# MCU.net
KiCad netlist of a schematic drawn in Altium Designer
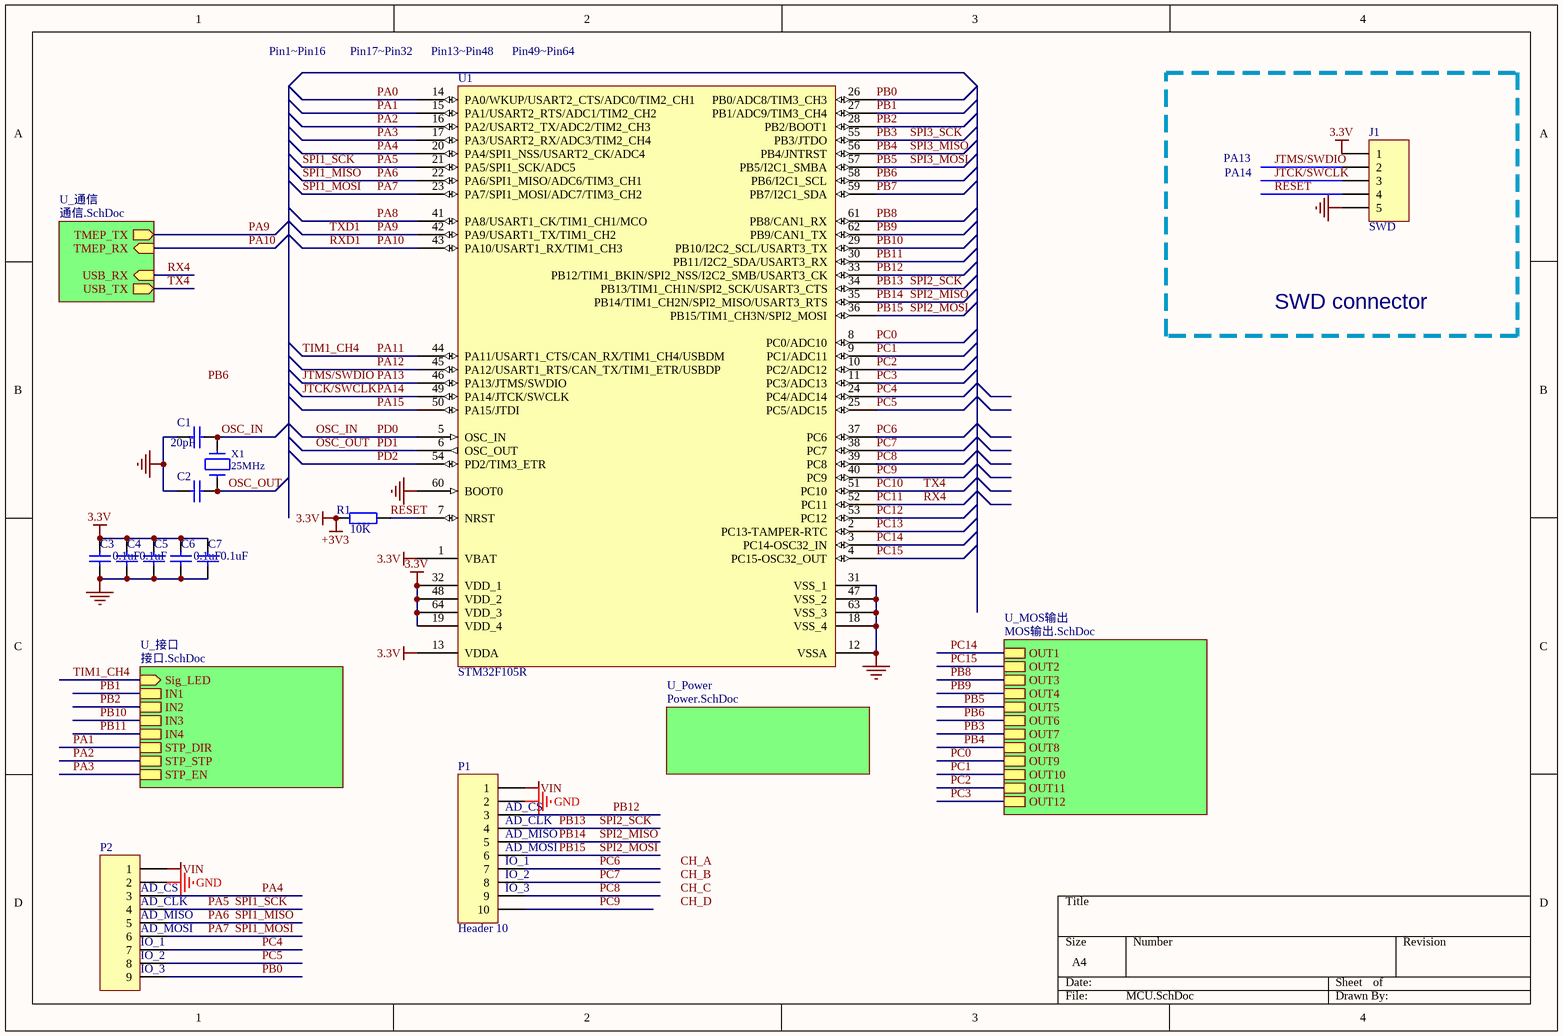
[diagram p0: MCU.SchDoc]

(export (version "E")
  (design (tool "Eeschema 10.0.6"))
  (components
    (comp (ref "C1")
      (value "20pF")
      (footprint "1608C")
      (description "Capacitor")
      (fields (field (name "PUBLISHER") "Altium Limited"))
      (libsource (lib "*") (part "Cap"))
    )
    (comp (ref "C2")
      (value "20pF")
      (footprint "1608C")
      (description "Capacitor")
      (fields (field (name "PUBLISHER") "Altium Limited"))
      (libsource (lib "*") (part "Cap"))
    )
    (comp (ref "C3")
      (value "0.1uF")
      (footprint "1608C")
      (description "Capacitor")
      (fields (field (name "PUBLISHER") "Altium Limited"))
      (libsource (lib "*") (part "Cap"))
    )
    (comp (ref "C4")
      (value "0.1uF")
      (footprint "1608C")
      (description "Capacitor")
      (fields (field (name "PUBLISHER") "Altium Limited"))
      (libsource (lib "*") (part "Cap"))
    )
    (comp (ref "C5")
      (value "0.1uF")
      (footprint "1608C")
      (description "Capacitor")
      (fields (field (name "PUBLISHER") "Altium Limited"))
      (libsource (lib "*") (part "Cap"))
    )
    (comp (ref "C6")
      (value "0.1uF")
      (footprint "1608C")
      (description "Capacitor")
      (fields (field (name "PUBLISHER") "Altium Limited"))
      (libsource (lib "*") (part "Cap"))
    )
    (comp (ref "C7")
      (value "0.1uF")
      (footprint "1608C")
      (description "Capacitor")
      (fields (field (name "PUBLISHER") "Altium Limited"))
      (libsource (lib "*") (part "Cap"))
    )
    (comp (ref "J1")
      (value "SWD")
      (footprint "ch2.5/5")
      (description "Header, 5-Pin")
      (fields (field (name "PUBLISHER") "Altium Limited"))
      (libsource (lib "Miscellaneous Connectors") (part "Header 5"))
    )
    (comp (ref "P1")
      (value "Header 10")
      (footprint "FPC-10B")
      (description "Header, 10-Pin")
      (fields (field (name "PUBLISHER") "Altium Limited"))
      (libsource (lib "Miscellaneous Connectors") (part "Header 10"))
    )
    (comp (ref "P2")
      (value "Header 9")
      (footprint "FPC-9B")
      (description "Header, 9-Pin")
      (fields (field (name "PUBLISHER") "Altium Limited"))
      (libsource (lib "Miscellaneous Connectors") (part "Header 9"))
    )
    (comp (ref "R1")
      (value "10K")
      (footprint "1608")
      (description "Resistor")
      (fields (field (name "PUBLISHER") "Altium Limited"))
      (libsource (lib "*") (part "Res2"))
    )
    (comp (ref "U1")
      (value "STM32F105R")
      (footprint "LQFP64_M")
      (libsource (lib "Schlib1") (part "STM32F105R"))
    )
    (comp (ref "X1") (value "25MHz") (footprint "SMD2_50X32") (libsource (lib "*") (part "CRYSTAL")))
  )
  (nets
    (net (code "1") (name "+3V3") (class "Default")
      (node (ref "C3") (pin "2") (pinfunction "2_2") (pintype "passive"))
      (node (ref "C4") (pin "2") (pinfunction "2_2") (pintype "passive"))
      (node (ref "C5") (pin "2") (pinfunction "2_2") (pintype "passive"))
      (node (ref "C6") (pin "2") (pinfunction "2_2") (pintype "passive"))
      (node (ref "C7") (pin "2") (pinfunction "2_2") (pintype "passive"))
      (node (ref "J1") (pin "1") (pinfunction "1_1") (pintype "passive"))
      (node (ref "R1") (pin "1") (pinfunction "1_1") (pintype "passive"))
      (node (ref "U1") (pin "1") (pinfunction "VBAT_1") (pintype "power_in"))
      (node (ref "U1") (pin "13") (pinfunction "VDDA_13") (pintype "power_in"))
      (node (ref "U1") (pin "19") (pinfunction "VDD_4_19") (pintype "power_in"))
      (node (ref "U1") (pin "32") (pinfunction "VDD_1_32") (pintype "power_in"))
      (node (ref "U1") (pin "48") (pinfunction "VDD_2_48") (pintype "power_in"))
      (node (ref "U1") (pin "64") (pinfunction "VDD_3_64") (pintype "power_in"))
    )
    (net (code "6") (name "/JTCK{slash}SWCLK") (class "Default")
      (node (ref "J1") (pin "3") (pinfunction "3_3") (pintype "passive"))
      (node (ref "U1") (pin "49") (pinfunction "PA14/JTCK/SWCLK_49") (pintype "bidirectional"))
    )
    (net (code "7") (name "/JTMS{slash}SWDIO") (class "Default")
      (node (ref "J1") (pin "2") (pinfunction "2_2") (pintype "passive"))
      (node (ref "U1") (pin "46") (pinfunction "PA13/JTMS/SWDIO_46") (pintype "bidirectional"))
    )
    (net (code "8") (name "/OSC_IN") (class "Default")
      (node (ref "C1") (pin "1") (pinfunction "1_1") (pintype "passive"))
      (node (ref "U1") (pin "5") (pinfunction "OSC_IN_5") (pintype "input"))
      (node (ref "X1") (pin "2") (pintype "passive"))
    )
    (net (code "9") (name "/OSC_OUT") (class "Default")
      (node (ref "C2") (pin "1") (pinfunction "1_1") (pintype "passive"))
      (node (ref "U1") (pin "6") (pinfunction "OSC_OUT_6") (pintype "output"))
      (node (ref "X1") (pin "1") (pintype "passive"))
    )
    (net (code "10") (name "/PA0") (class "Default")
      (node (ref "U1") (pin "14") (pinfunction "PA0/WKUP/USART2_CTS/ADC0/TIM2_CH1_14") (pintype "bidirectional"))
    )
    (net (code "11") (name "/PA1") (class "Default")
      (node (ref "U1") (pin "15") (pinfunction "PA1/USART2_RTS/ADC1/TIM2_CH2_15") (pintype "bidirectional"))
    )
    (net (code "12") (name "/PA2") (class "Default")
      (node (ref "U1") (pin "16") (pinfunction "PA2/USART2_TX/ADC2/TIM2_CH3_16") (pintype "bidirectional"))
    )
    (net (code "13") (name "/PA3") (class "Default")
      (node (ref "U1") (pin "17") (pinfunction "PA3/USART2_RX/ADC3/TIM2_CH4_17") (pintype "bidirectional"))
    )
    (net (code "14") (name "/PA4") (class "Default")
      (node (ref "P2") (pin "3") (pinfunction "3_3") (pintype "passive"))
      (node (ref "U1") (pin "20") (pinfunction "PA4/SPI1_NSS/USART2_CK/ADC4_20") (pintype "bidirectional"))
    )
    (net (code "15") (name "/PA5") (class "Default")
      (node (ref "P2") (pin "4") (pinfunction "4_4") (pintype "passive"))
      (node (ref "U1") (pin "21") (pinfunction "PA5/SPI1_SCK/ADC5_21") (pintype "bidirectional"))
    )
    (net (code "16") (name "/PA6") (class "Default")
      (node (ref "P2") (pin "5") (pinfunction "5_5") (pintype "passive"))
      (node (ref "U1") (pin "22") (pinfunction "PA6/SPI1_MISO/ADC6/TIM3_CH1_22") (pintype "bidirectional"))
    )
    (net (code "17") (name "/PA7") (class "Default")
      (node (ref "P2") (pin "6") (pinfunction "6_6") (pintype "passive"))
      (node (ref "U1") (pin "23") (pinfunction "PA7/SPI1_MOSI/ADC7/TIM3_CH2_23") (pintype "bidirectional"))
    )
    (net (code "18") (name "/PA8") (class "Default")
      (node (ref "U1") (pin "41") (pinfunction "PA8/USART1_CK/TIM1_CH1/MCO_41") (pintype "bidirectional"))
    )
    (net (code "19") (name "/PA9") (class "Default")
      (node (ref "U1") (pin "42") (pinfunction "PA9/USART1_TX/TIM1_CH2_42") (pintype "bidirectional"))
    )
    (net (code "20") (name "/PA10") (class "Default")
      (node (ref "U1") (pin "43") (pinfunction "PA10/USART1_RX/TIM1_CH3_43") (pintype "bidirectional"))
    )
    (net (code "21") (name "/PA11") (class "Default")
      (node (ref "U1") (pin "44") (pinfunction "PA11/USART1_CTS/CAN_RX/TIM1_CH4/USBDM_44") (pintype "bidirectional"))
    )
    (net (code "22") (name "/PA12") (class "Default")
      (node (ref "U1") (pin "45") (pinfunction "PA12/USART1_RTS/CAN_TX/TIM1_ETR/USBDP_45") (pintype "bidirectional"))
    )
    (net (code "23") (name "/PA15") (class "Default")
      (node (ref "U1") (pin "50") (pinfunction "PA15/JTDI_50") (pintype "bidirectional"))
    )
    (net (code "24") (name "/PB0") (class "Default")
      (node (ref "P2") (pin "9") (pinfunction "9_9") (pintype "passive"))
      (node (ref "U1") (pin "26") (pinfunction "PB0/ADC8/TIM3_CH3_26") (pintype "bidirectional"))
    )
    (net (code "25") (name "/PB1") (class "Default")
      (node (ref "U1") (pin "27") (pinfunction "PB1/ADC9/TIM3_CH4_27") (pintype "bidirectional"))
    )
    (net (code "26") (name "/PB2") (class "Default")
      (node (ref "U1") (pin "28") (pinfunction "PB2/BOOT1_28") (pintype "bidirectional"))
    )
    (net (code "27") (name "/PB3") (class "Default")
      (node (ref "U1") (pin "55") (pinfunction "PB3/JTDO_55") (pintype "bidirectional"))
    )
    (net (code "28") (name "/PB4") (class "Default")
      (node (ref "U1") (pin "56") (pinfunction "PB4/JNTRST_56") (pintype "bidirectional"))
    )
    (net (code "29") (name "/PB5") (class "Default")
      (node (ref "U1") (pin "57") (pinfunction "PB5/I2C1_SMBA_57") (pintype "bidirectional"))
    )
    (net (code "30") (name "/PB6") (class "Default")
      (node (ref "U1") (pin "58") (pinfunction "PB6/I2C1_SCL_58") (pintype "bidirectional"))
    )
    (net (code "31") (name "/PB7") (class "Default")
      (node (ref "U1") (pin "59") (pinfunction "PB7/I2C1_SDA_59") (pintype "bidirectional"))
    )
    (net (code "32") (name "/PB8") (class "Default")
      (node (ref "U1") (pin "61") (pinfunction "PB8/CAN1_RX_61") (pintype "bidirectional"))
    )
    (net (code "33") (name "/PB9") (class "Default")
      (node (ref "U1") (pin "62") (pinfunction "PB9/CAN1_TX_62") (pintype "bidirectional"))
    )
    (net (code "34") (name "/PB10") (class "Default")
      (node (ref "U1") (pin "29") (pinfunction "PB10/I2C2_SCL/USART3_TX_29") (pintype "bidirectional"))
    )
    (net (code "35") (name "/PB11") (class "Default")
      (node (ref "U1") (pin "30") (pinfunction "PB11/I2C2_SDA/USART3_RX_30") (pintype "bidirectional"))
    )
    (net (code "36") (name "/PB12") (class "Default")
      (node (ref "P1") (pin "3") (pinfunction "3_3") (pintype "passive"))
      (node (ref "U1") (pin "33") (pinfunction "PB12/TIM1_BKIN/SPI2_NSS/I2C2_SMB/USART3_CK_33") (pintype "bidirectional"))
    )
    (net (code "37") (name "/PB13") (class "Default")
      (node (ref "P1") (pin "4") (pinfunction "4_4") (pintype "passive"))
      (node (ref "U1") (pin "34") (pinfunction "PB13/TIM1_CH1N/SPI2_SCK/USART3_CTS_34") (pintype "bidirectional"))
    )
    (net (code "38") (name "/PB14") (class "Default")
      (node (ref "P1") (pin "5") (pinfunction "5_5") (pintype "passive"))
      (node (ref "U1") (pin "35") (pinfunction "PB14/TIM1_CH2N/SPI2_MISO/USART3_RTS_35") (pintype "bidirectional"))
    )
    (net (code "39") (name "/PB15") (class "Default")
      (node (ref "P1") (pin "6") (pinfunction "6_6") (pintype "passive"))
      (node (ref "U1") (pin "36") (pinfunction "PB15/TIM1_CH3N/SPI2_MOSI_36") (pintype "bidirectional"))
    )
    (net (code "40") (name "/PC0") (class "Default")
      (node (ref "U1") (pin "8") (pinfunction "PC0/ADC10_8") (pintype "bidirectional"))
    )
    (net (code "41") (name "/PC1") (class "Default")
      (node (ref "U1") (pin "9") (pinfunction "PC1/ADC11_9") (pintype "bidirectional"))
    )
    (net (code "42") (name "/PC2") (class "Default")
      (node (ref "U1") (pin "10") (pinfunction "PC2/ADC12_10") (pintype "bidirectional"))
    )
    (net (code "43") (name "/PC3") (class "Default")
      (node (ref "U1") (pin "11") (pinfunction "PC3/ADC13_11") (pintype "bidirectional"))
    )
    (net (code "44") (name "/PC4") (class "Default")
      (node (ref "P2") (pin "7") (pinfunction "7_7") (pintype "passive"))
      (node (ref "U1") (pin "24") (pinfunction "PC4/ADC14_24") (pintype "bidirectional"))
    )
    (net (code "45") (name "/PC5") (class "Default")
      (node (ref "P2") (pin "8") (pinfunction "8_8") (pintype "passive"))
      (node (ref "U1") (pin "25") (pinfunction "PC5/ADC15_25") (pintype "bidirectional"))
    )
    (net (code "46") (name "/PC6") (class "Default")
      (node (ref "P1") (pin "7") (pinfunction "7_7") (pintype "passive"))
      (node (ref "U1") (pin "37") (pinfunction "PC6_37") (pintype "bidirectional"))
    )
    (net (code "47") (name "/PC7") (class "Default")
      (node (ref "P1") (pin "8") (pinfunction "8_8") (pintype "passive"))
      (node (ref "U1") (pin "38") (pinfunction "PC7_38") (pintype "bidirectional"))
    )
    (net (code "48") (name "/PC8") (class "Default")
      (node (ref "P1") (pin "9") (pinfunction "9_9") (pintype "passive"))
      (node (ref "U1") (pin "39") (pinfunction "PC8_39") (pintype "bidirectional"))
    )
    (net (code "49") (name "/PC9") (class "Default")
      (node (ref "P1") (pin "10") (pinfunction "10_10") (pintype "passive"))
      (node (ref "U1") (pin "40") (pinfunction "PC9_40") (pintype "bidirectional"))
    )
    (net (code "50") (name "/PC10") (class "Default")
      (node (ref "U1") (pin "51") (pinfunction "PC10_51") (pintype "bidirectional"))
    )
    (net (code "51") (name "/PC11") (class "Default")
      (node (ref "U1") (pin "52") (pinfunction "PC11_52") (pintype "bidirectional"))
    )
    (net (code "52") (name "/PC12") (class "Default")
      (node (ref "U1") (pin "53") (pinfunction "PC12_53") (pintype "bidirectional"))
    )
    (net (code "53") (name "/PC13") (class "Default")
      (node (ref "U1") (pin "2") (pinfunction "PC13-TAMPER-RTC_2") (pintype "bidirectional"))
    )
    (net (code "54") (name "/PC14") (class "Default")
      (node (ref "U1") (pin "3") (pinfunction "PC14-OSC32_IN_3") (pintype "bidirectional"))
    )
    (net (code "55") (name "/PC15") (class "Default")
      (node (ref "U1") (pin "4") (pinfunction "PC15-OSC32_OUT_4") (pintype "bidirectional"))
    )
    (net (code "56") (name "/PD2") (class "Default")
      (node (ref "U1") (pin "54") (pinfunction "PD2/TIM3_ETR_54") (pintype "bidirectional"))
    )
    (net (code "57") (name "/RESET") (class "Default")
      (node (ref "J1") (pin "4") (pinfunction "4_4") (pintype "passive"))
      (node (ref "R1") (pin "2") (pinfunction "2_2") (pintype "passive"))
      (node (ref "U1") (pin "7") (pinfunction "NRST_7") (pintype "bidirectional"))
    )
    (net (code "58") (name "GND") (class "Default")
      (node (ref "C1") (pin "2") (pinfunction "2_2") (pintype "passive"))
      (node (ref "C2") (pin "2") (pinfunction "2_2") (pintype "passive"))
      (node (ref "C3") (pin "1") (pinfunction "1_1") (pintype "passive"))
      (node (ref "C4") (pin "1") (pinfunction "1_1") (pintype "passive"))
      (node (ref "C5") (pin "1") (pinfunction "1_1") (pintype "passive"))
      (node (ref "C6") (pin "1") (pinfunction "1_1") (pintype "passive"))
      (node (ref "C7") (pin "1") (pinfunction "1_1") (pintype "passive"))
      (node (ref "J1") (pin "5") (pinfunction "5_5") (pintype "passive"))
      (node (ref "P1") (pin "2") (pinfunction "2_2") (pintype "passive"))
      (node (ref "P2") (pin "2") (pinfunction "2_2") (pintype "passive"))
      (node (ref "U1") (pin "12") (pinfunction "VSSA_12") (pintype "power_in"))
      (node (ref "U1") (pin "18") (pinfunction "VSS_4_18") (pintype "power_in"))
      (node (ref "U1") (pin "31") (pinfunction "VSS_1_31") (pintype "power_in"))
      (node (ref "U1") (pin "47") (pinfunction "VSS_2_47") (pintype "power_in"))
      (node (ref "U1") (pin "60") (pinfunction "BOOT0_60") (pintype "input"))
      (node (ref "U1") (pin "63") (pinfunction "VSS_3_63") (pintype "power_in"))
    )
    (net (code "59") (name "VIN") (class "Default")
      (node (ref "P1") (pin "1") (pinfunction "1_1") (pintype "passive"))
      (node (ref "P2") (pin "1") (pinfunction "1_1") (pintype "passive"))
    )
  )
)
